# MosFets.net
KiCad netlist of a schematic drawn in Altium Designer
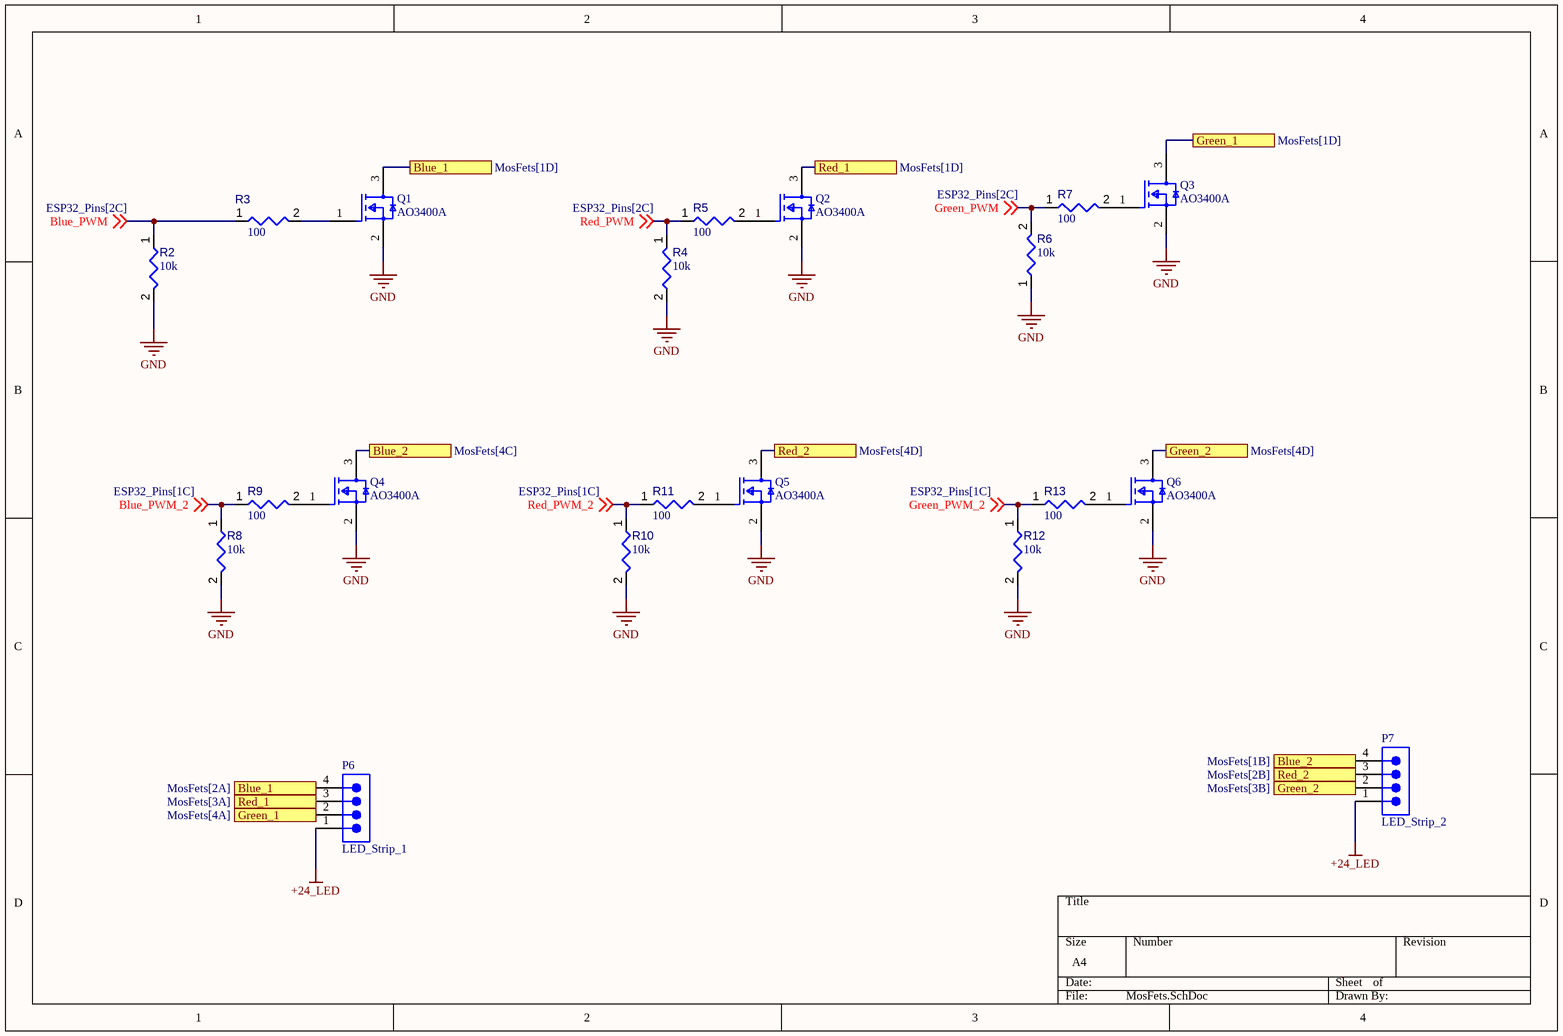
[diagram p0: MosFets.SchDoc]

(export (version "E")
  (design (tool "Eeschema 10.0.6"))
  (components
    (comp (ref "P6")
      (value "LED_Strip_1")
      (footprint "SMTC-TSW-104-08-X-S")
      (description "Conn Unshrouded Header HDR 4 POS 2.54mm Solder ST Top Entry Thru-Hole Bulk")
      (libsource (lib "Hood") (part "SMTC-TSW-104-08-X-S"))
    )
    (comp (ref "P7")
      (value "LED_Strip_2")
      (footprint "SMTC-TSW-104-08-X-S")
      (description "Conn Unshrouded Header HDR 4 POS 2.54mm Solder ST Top Entry Thru-Hole Bulk")
      (libsource (lib "Hood") (part "SMTC-TSW-104-08-X-S"))
    )
    (comp (ref "Q1")
      (value "AO3400A")
      (footprint "FP-SOT23-IPC_C")
      (fields (field (name "JLCPCB PART #") "C20917") (field (name "MANUFACTURER") "Alpha & Omega Semicon"))
      (libsource (lib "Hood") (part "0a9ea7c96deaaede766a5b531c28de0"))
    )
    (comp (ref "Q2")
      (value "AO3400A")
      (footprint "FP-SOT23-IPC_C")
      (description "Trans MOSFET N-CH 30V 5.7A 3-Pin SOT-23")
      (libsource (lib "Hood") (part "0a9ea7c96deaaede766a5b531c28de0"))
    )
    (comp (ref "Q3")
      (value "AO3400A")
      (footprint "FP-SOT23-IPC_C")
      (description "Trans MOSFET N-CH 30V 5.7A 3-Pin SOT-23")
      (libsource (lib "Hood") (part "0a9ea7c96deaaede766a5b531c28de0"))
    )
    (comp (ref "Q4")
      (value "AO3400A")
      (footprint "FP-SOT23-IPC_C")
      (description "Trans MOSFET N-CH 30V 5.7A 3-Pin SOT-23")
      (libsource (lib "Hood") (part "0a9ea7c96deaaede766a5b531c28de0"))
    )
    (comp (ref "Q5")
      (value "AO3400A")
      (footprint "FP-SOT23-IPC_C")
      (description "Trans MOSFET N-CH 30V 5.7A 3-Pin SOT-23")
      (libsource (lib "Hood") (part "0a9ea7c96deaaede766a5b531c28de0"))
    )
    (comp (ref "Q6")
      (value "AO3400A")
      (footprint "FP-SOT23-IPC_C")
      (description "Trans MOSFET N-CH 30V 5.7A 3-Pin SOT-23")
      (libsource (lib "Hood") (part "0a9ea7c96deaaede766a5b531c28de0"))
    )
    (comp (ref "R2")
      (value "10k")
      (footprint "FP-AC0603-IPC_C")
      (description "Res Thick Film 0603 10K Ohm 1% 0.1W(1/10W) ±100ppm/C Pad SMD")
      (fields (field (name "TOLERANCE") "5%") (field (name "Comment") "0603WAF1002T5E"))
      (libsource (lib "Hood") (part "RES-2"))
    )
    (comp (ref "R3")
      (value "100")
      (footprint "FP-AC0603-IPC_C")
      (fields
        (field (name "POWER") "100mW")
        (field (name "JLCPCB PART #") "C22775")
        (field (name "MFR.PART #") "0603WAF1000T5E")
      )
      (libsource (lib "Hood") (part "RES-2"))
    )
    (comp (ref "R4")
      (value "10k")
      (footprint "FP-AC0603-IPC_C")
      (description "Res Thick Film 0603 10K Ohm 1% 0.1W(1/10W) ±100ppm/C Pad SMD")
      (fields (field (name "TOLERANCE") "5%") (field (name "Comment") "0603WAF1002T5E"))
      (libsource (lib "") (part "RES-2_1"))
    )
    (comp (ref "R5")
      (value "100")
      (footprint "FP-AC0603-IPC_C")
      (fields
        (field (name "POWER") "100mW")
        (field (name "JLCPCB PART #") "C22775")
        (field (name "MFR.PART #") "0603WAF1000T5E")
      )
      (libsource (lib "Hood") (part "RES-2"))
    )
    (comp (ref "R6")
      (value "10k")
      (footprint "FP-AC0603-IPC_C")
      (description "Res Thick Film 0603 10K Ohm 1% 0.1W(1/10W) ±100ppm/C Pad SMD")
      (fields (field (name "TOLERANCE") "5%") (field (name "JLCPCB PART #") "C25804"))
      (libsource (lib "Hood") (part "RES-2"))
    )
    (comp (ref "R7")
      (value "100")
      (footprint "FP-AC0603-IPC_C")
      (fields
        (field (name "POWER") "100mW")
        (field (name "JLCPCB PART #") "C22775")
        (field (name "MFR.PART #") "0603WAF1000T5E")
      )
      (libsource (lib "Hood") (part "RES-2"))
    )
    (comp (ref "R8")
      (value "10k")
      (footprint "FP-AC0603-IPC_C")
      (description "Res Thick Film 0603 10K Ohm 1% 0.1W(1/10W) ±100ppm/C Pad SMD")
      (fields (field (name "TOLERANCE") "5%") (field (name "Comment") "0603WAF1002T5E"))
      (libsource (lib "Hood") (part "RES-2"))
    )
    (comp (ref "R9")
      (value "100")
      (footprint "FP-AC0603-IPC_C")
      (fields
        (field (name "POWER") "100mW")
        (field (name "JLCPCB PART #") "C22775")
        (field (name "MFR.PART #") "0603WAF1000T5E")
      )
      (libsource (lib "Hood") (part "RES-2"))
    )
    (comp (ref "R10")
      (value "10k")
      (footprint "FP-AC0603-IPC_C")
      (description "Res Thick Film 0603 10K Ohm 1% 0.1W(1/10W) ±100ppm/C Pad SMD")
      (fields (field (name "TOLERANCE") "5%") (field (name "Comment") "0603WAF1002T5E"))
      (libsource (lib "Hood") (part "RES-2"))
    )
    (comp (ref "R11")
      (value "100")
      (footprint "FP-AC0603-IPC_C")
      (fields
        (field (name "POWER") "100mW")
        (field (name "JLCPCB PART #") "C22775")
        (field (name "MFR.PART #") "0603WAF1000T5E")
      )
      (libsource (lib "Hood") (part "RES-2"))
    )
    (comp (ref "R12")
      (value "10k")
      (footprint "FP-AC0603-IPC_C")
      (description "Res Thick Film 0603 10K Ohm 1% 0.1W(1/10W) ±100ppm/C Pad SMD")
      (fields (field (name "TOLERANCE") "5%") (field (name "Comment") "0603WAF1002T5E"))
      (libsource (lib "Hood") (part "RES-2"))
    )
    (comp (ref "R13")
      (value "100")
      (footprint "FP-AC0603-IPC_C")
      (fields
        (field (name "POWER") "100mW")
        (field (name "JLCPCB PART #") "C22775")
        (field (name "MFR.PART #") "0603WAF1000T5E")
      )
      (libsource (lib "Hood") (part "RES-2"))
    )
  )
  (nets
    (net (code "1") (name "+24_LED") (class "Default")
      (node (ref "P6") (pin "1") (pinfunction "1_1") (pintype "passive"))
      (node (ref "P7") (pin "1") (pinfunction "1_1") (pintype "passive"))
    )
    (net (code "2") (name "/Blue_1") (class "Default")
      (node (ref "P6") (pin "4") (pinfunction "4_4") (pintype "passive"))
      (node (ref "Q1") (pin "3") (pinfunction "D_3") (pintype "passive"))
    )
    (net (code "3") (name "/Blue_2") (class "Default")
      (node (ref "P7") (pin "4") (pinfunction "4_4") (pintype "passive"))
      (node (ref "Q4") (pin "3") (pinfunction "D_3") (pintype "passive"))
    )
    (net (code "4") (name "/Green_1") (class "Default")
      (node (ref "P6") (pin "2") (pinfunction "2_2") (pintype "passive"))
      (node (ref "Q3") (pin "3") (pinfunction "D_3") (pintype "passive"))
    )
    (net (code "5") (name "/Green_2") (class "Default")
      (node (ref "P7") (pin "2") (pinfunction "2_2") (pintype "passive"))
      (node (ref "Q6") (pin "3") (pinfunction "D_3") (pintype "passive"))
    )
    (net (code "6") (name "/Red_1") (class "Default")
      (node (ref "P6") (pin "3") (pinfunction "3_3") (pintype "passive"))
      (node (ref "Q2") (pin "3") (pinfunction "D_3") (pintype "passive"))
    )
    (net (code "7") (name "/Red_2") (class "Default")
      (node (ref "P7") (pin "3") (pinfunction "3_3") (pintype "passive"))
      (node (ref "Q5") (pin "3") (pinfunction "D_3") (pintype "passive"))
    )
    (net (code "8") (name "Blue_PWM") (class "Default")
      (node (ref "R2") (pin "1") (pinfunction "1_1") (pintype "passive"))
      (node (ref "R3") (pin "1") (pinfunction "1_1") (pintype "passive"))
    )
    (net (code "9") (name "Blue_PWM_2") (class "Default")
      (node (ref "R8") (pin "1") (pinfunction "1_1") (pintype "passive"))
      (node (ref "R9") (pin "1") (pinfunction "1_1") (pintype "passive"))
    )
    (net (code "10") (name "GND") (class "Default")
      (node (ref "Q1") (pin "2") (pinfunction "S_2") (pintype "passive"))
      (node (ref "Q2") (pin "2") (pinfunction "S_2") (pintype "passive"))
      (node (ref "Q3") (pin "2") (pinfunction "S_2") (pintype "passive"))
      (node (ref "Q4") (pin "2") (pinfunction "S_2") (pintype "passive"))
      (node (ref "Q5") (pin "2") (pinfunction "S_2") (pintype "passive"))
      (node (ref "Q6") (pin "2") (pinfunction "S_2") (pintype "passive"))
      (node (ref "R10") (pin "2") (pinfunction "2_2") (pintype "passive"))
      (node (ref "R12") (pin "2") (pinfunction "2_2") (pintype "passive"))
      (node (ref "R2") (pin "2") (pinfunction "2_2") (pintype "passive"))
      (node (ref "R4") (pin "2") (pinfunction "2_2") (pintype "passive"))
      (node (ref "R6") (pin "1") (pinfunction "1_1") (pintype "passive"))
      (node (ref "R8") (pin "2") (pinfunction "2_2") (pintype "passive"))
    )
    (net (code "11") (name "Green_PWM") (class "Default")
      (node (ref "R6") (pin "2") (pinfunction "2_2") (pintype "passive"))
      (node (ref "R7") (pin "1") (pinfunction "1_1") (pintype "passive"))
    )
    (net (code "12") (name "Green_PWM_2") (class "Default")
      (node (ref "R12") (pin "1") (pinfunction "1_1") (pintype "passive"))
      (node (ref "R13") (pin "1") (pinfunction "1_1") (pintype "passive"))
    )
    (net (code "13") (name "Net-(Q1-G)") (class "Default")
      (node (ref "Q1") (pin "1") (pinfunction "G_1") (pintype "passive"))
      (node (ref "R3") (pin "2") (pinfunction "2_2") (pintype "passive"))
    )
    (net (code "14") (name "Net-(Q2-G)") (class "Default")
      (node (ref "Q2") (pin "1") (pinfunction "G_1") (pintype "passive"))
      (node (ref "R5") (pin "2") (pinfunction "2_2") (pintype "passive"))
    )
    (net (code "15") (name "Net-(Q3-G)") (class "Default")
      (node (ref "Q3") (pin "1") (pinfunction "G_1") (pintype "passive"))
      (node (ref "R7") (pin "2") (pinfunction "2_2") (pintype "passive"))
    )
    (net (code "16") (name "Net-(Q4-G)") (class "Default")
      (node (ref "Q4") (pin "1") (pinfunction "G_1") (pintype "passive"))
      (node (ref "R9") (pin "2") (pinfunction "2_2") (pintype "passive"))
    )
    (net (code "17") (name "Net-(Q5-G)") (class "Default")
      (node (ref "Q5") (pin "1") (pinfunction "G_1") (pintype "passive"))
      (node (ref "R11") (pin "2") (pinfunction "2_2") (pintype "passive"))
    )
    (net (code "18") (name "Net-(Q6-G)") (class "Default")
      (node (ref "Q6") (pin "1") (pinfunction "G_1") (pintype "passive"))
      (node (ref "R13") (pin "2") (pinfunction "2_2") (pintype "passive"))
    )
    (net (code "19") (name "Red_PWM") (class "Default")
      (node (ref "R4") (pin "1") (pinfunction "1_1") (pintype "passive"))
      (node (ref "R5") (pin "1") (pinfunction "1_1") (pintype "passive"))
    )
    (net (code "20") (name "Red_PWM_2") (class "Default")
      (node (ref "R10") (pin "1") (pinfunction "1_1") (pintype "passive"))
      (node (ref "R11") (pin "1") (pinfunction "1_1") (pintype "passive"))
    )
  )
)
